# DC_motor_driver.net
KiCad netlist of a schematic drawn in Altium Designer
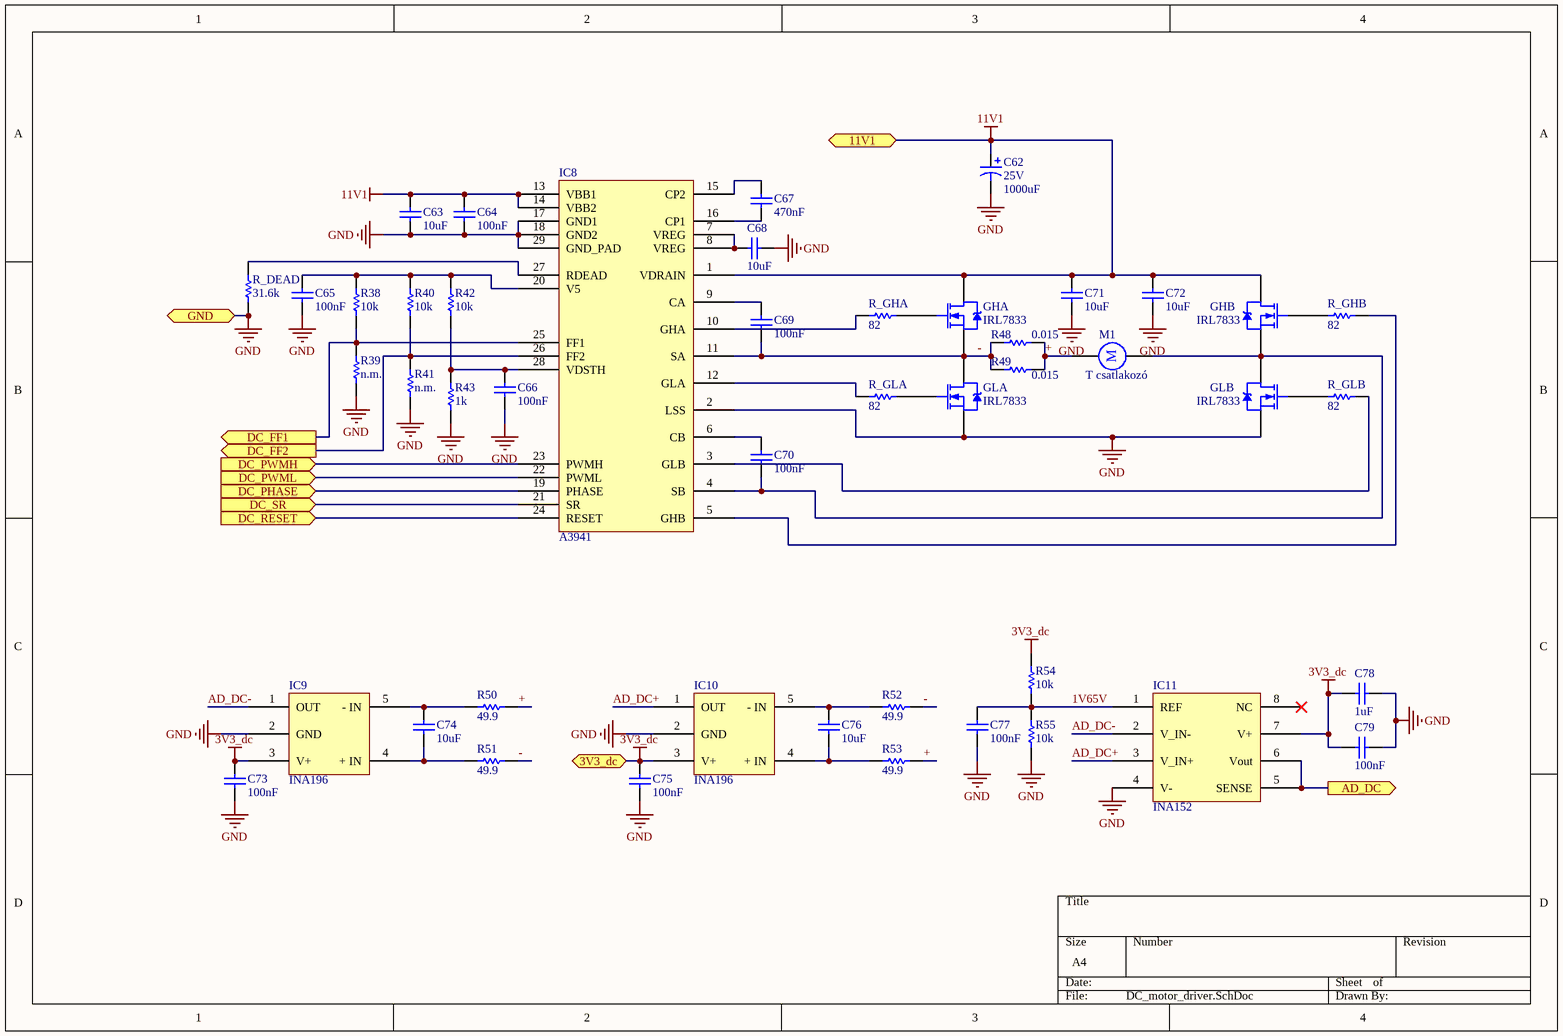
[diagram p0: DC_motor_driver.SchDoc]

(export (version "E")
  (design (tool "Eeschema 10.0.6"))
  (components
    (comp (ref "C62")
      (value "25V")
      (footprint "power_cap_13mm")
      (description "Polarized Capacitor (Radial)")
      (fields (field (name "ALTIUM_VALUE") "1000uF") (field (name "PUBLISHER") "Altium Limited"))
      (libsource (lib "Miscellaneous Devices") (part "Cap Pol1"))
    )
    (comp (ref "C63")
      (value "10uF")
      (footprint "FP_1206_CAP_125")
      (description "Capacitor")
      (fields (field (name "Comment") "Cap") (field (name "PUBLISHER") "Altium Limited"))
      (libsource (lib "Miscellaneous Devices") (part "Cap"))
    )
    (comp (ref "C64")
      (value "100nF")
      (footprint "FP_0603_CAP_080")
      (description "Capacitor")
      (fields (field (name "Comment") "Cap") (field (name "PUBLISHER") "Altium Limited"))
      (libsource (lib "Miscellaneous Devices") (part "Cap"))
    )
    (comp (ref "C65")
      (value "100nF")
      (footprint "FP_0603_CAP_080")
      (description "Capacitor")
      (fields (field (name "Comment") "Cap") (field (name "PUBLISHER") "Altium Limited"))
      (libsource (lib "Miscellaneous Devices") (part "Cap"))
    )
    (comp (ref "C66")
      (value "100nF")
      (footprint "FP_0603_CAP_080")
      (description "Capacitor")
      (fields (field (name "Comment") "Cap") (field (name "PUBLISHER") "Altium Limited"))
      (libsource (lib "Miscellaneous Devices") (part "Cap"))
    )
    (comp (ref "C67")
      (value "470nF")
      (footprint "FP_0603_CAP_080")
      (description "Capacitor")
      (fields (field (name "Comment") "Cap") (field (name "PUBLISHER") "Altium Limited"))
      (libsource (lib "Miscellaneous Devices") (part "Cap"))
    )
    (comp (ref "C68")
      (value "10uF")
      (footprint "FP_1206_CAP_125")
      (description "Capacitor")
      (fields (field (name "Comment") "Cap") (field (name "PUBLISHER") "Altium Limited"))
      (libsource (lib "Miscellaneous Devices") (part "Cap"))
    )
    (comp (ref "C69")
      (value "100nF")
      (footprint "FP_0603_CAP_080")
      (description "Capacitor")
      (fields (field (name "Comment") "Cap") (field (name "PUBLISHER") "Altium Limited"))
      (libsource (lib "Miscellaneous Devices") (part "Cap"))
    )
    (comp (ref "C70")
      (value "100nF")
      (footprint "FP_0603_CAP_080")
      (description "Capacitor")
      (fields (field (name "Comment") "Cap") (field (name "PUBLISHER") "Altium Limited"))
      (libsource (lib "Miscellaneous Devices") (part "Cap"))
    )
    (comp (ref "C71")
      (value "10uF")
      (footprint "FP_1206_CAP_125")
      (description "Capacitor")
      (fields (field (name "Comment") "Cap") (field (name "PUBLISHER") "Altium Limited"))
      (libsource (lib "Miscellaneous Devices") (part "Cap"))
    )
    (comp (ref "C72")
      (value "10uF")
      (footprint "FP_1206_CAP_125")
      (description "Capacitor")
      (fields (field (name "Comment") "Cap") (field (name "PUBLISHER") "Altium Limited"))
      (libsource (lib "Miscellaneous Devices") (part "Cap"))
    )
    (comp (ref "C73")
      (value "100nF")
      (footprint "FP_0603_CAP_080")
      (description "Capacitor")
      (fields (field (name "Comment") "Cap") (field (name "PUBLISHER") "Altium Limited"))
      (libsource (lib "Miscellaneous Devices") (part "Cap"))
    )
    (comp (ref "C74")
      (value "10uF")
      (footprint "FP_0603_CAP_080")
      (description "Capacitor")
      (fields (field (name "Comment") "Cap") (field (name "PUBLISHER") "Altium Limited"))
      (libsource (lib "Miscellaneous Devices") (part "Cap"))
    )
    (comp (ref "C75")
      (value "100nF")
      (footprint "FP_0603_CAP_080")
      (description "Capacitor")
      (fields (field (name "Comment") "Cap") (field (name "PUBLISHER") "Altium Limited"))
      (libsource (lib "Miscellaneous Devices") (part "Cap"))
    )
    (comp (ref "C76")
      (value "10uF")
      (footprint "FP_0603_CAP_080")
      (description "Capacitor")
      (fields (field (name "Comment") "Cap") (field (name "PUBLISHER") "Altium Limited"))
      (libsource (lib "Miscellaneous Devices") (part "Cap"))
    )
    (comp (ref "C77")
      (value "100nF")
      (footprint "FP_0603_CAP_080")
      (description "Capacitor")
      (fields (field (name "Comment") "Cap") (field (name "PUBLISHER") "Altium Limited"))
      (libsource (lib "Miscellaneous Devices") (part "Cap"))
    )
    (comp (ref "C78")
      (value "1uF")
      (footprint "FP_0603_CAP_080")
      (description "Capacitor")
      (fields (field (name "Comment") "Cap") (field (name "PUBLISHER") "Altium Limited"))
      (libsource (lib "Miscellaneous Devices") (part "Cap"))
    )
    (comp (ref "C79")
      (value "100nF")
      (footprint "FP_0603_CAP_080")
      (description "Capacitor")
      (fields (field (name "Comment") "Cap") (field (name "PUBLISHER") "Altium Limited"))
      (libsource (lib "Miscellaneous Devices") (part "Cap"))
    )
    (comp (ref "GHA")
      (value "IRL7833")
      (footprint "TO220AB")
      (description "N-Channel Power MOSFET")
      (fields (field (name "PUBLISHER") "Altium Limited"))
      (libsource (lib "Miscellaneous Devices") (part "NMOS-2"))
    )
    (comp (ref "GHB")
      (value "IRL7833")
      (footprint "TO220AB")
      (description "N-Channel Power MOSFET")
      (fields (field (name "PUBLISHER") "Altium Limited"))
      (libsource (lib "Miscellaneous Devices") (part "NMOS-2"))
    )
    (comp (ref "GLA")
      (value "IRL7833")
      (footprint "TO220AB")
      (description "N-Channel Power MOSFET")
      (fields (field (name "PUBLISHER") "Altium Limited"))
      (libsource (lib "Miscellaneous Devices") (part "NMOS-2"))
    )
    (comp (ref "GLB")
      (value "IRL7833")
      (footprint "TO220AB")
      (description "N-Channel Power MOSFET")
      (fields (field (name "PUBLISHER") "Altium Limited"))
      (libsource (lib "Miscellaneous Devices") (part "NMOS-2"))
    )
    (comp (ref "IC8")
      (value "A3941")
      (footprint "TSSOP28_thermal_pad")
      (libsource (lib "diploma") (part "A3941"))
    )
    (comp (ref "IC9") (value "INA196") (footprint "FP_SOT23-5") (libsource (lib "diploma") (part "INA196")))
    (comp (ref "IC10") (value "INA196") (footprint "FP_SOT23-5") (libsource (lib "diploma") (part "INA196")))
    (comp (ref "IC11") (value "INA152") (footprint "MSOP-MS8_M") (libsource (lib "diploma") (part "INA152")))
    (comp (ref "M1")
      (value "T csatlakozó")
      (footprint "T-csatlakozo")
      (description "Motor, General Kind")
      (fields (field (name "PUBLISHER") "Altium Limited"))
      (libsource (lib "Miscellaneous Devices") (part "Motor"))
    )
    (comp (ref "R38")
      (value "10k")
      (footprint "FP_0603_CAP_080")
      (description "Resistor")
      (fields (field (name "Comment") "Res1") (field (name "PUBLISHER") "Altium Limited"))
      (libsource (lib "Miscellaneous Devices") (part "Res1"))
    )
    (comp (ref "R39")
      (value "n.m.")
      (footprint "FP_0603_CAP_080")
      (description "Resistor")
      (fields (field (name "Comment") "Res1") (field (name "PUBLISHER") "Altium Limited"))
      (libsource (lib "Miscellaneous Devices") (part "Res1"))
    )
    (comp (ref "R40")
      (value "10k")
      (footprint "FP_0603_RES")
      (description "Resistor")
      (fields (field (name "Comment") "Res1") (field (name "PUBLISHER") "Altium Limited"))
      (libsource (lib "Miscellaneous Devices") (part "Res1"))
    )
    (comp (ref "R41")
      (value "n.m.")
      (footprint "FP_0603_RES")
      (description "Resistor")
      (fields (field (name "Comment") "Res1") (field (name "PUBLISHER") "Altium Limited"))
      (libsource (lib "Miscellaneous Devices") (part "Res1"))
    )
    (comp (ref "R42")
      (value "10k")
      (footprint "FP_0603_CAP_080")
      (description "Resistor")
      (fields (field (name "Comment") "Res1") (field (name "PUBLISHER") "Altium Limited"))
      (libsource (lib "Miscellaneous Devices") (part "Res1"))
    )
    (comp (ref "R43")
      (value "1k")
      (footprint "FP_0603_RES")
      (description "Resistor")
      (fields (field (name "Comment") "Res1") (field (name "PUBLISHER") "Altium Limited"))
      (libsource (lib "Miscellaneous Devices") (part "Res1"))
    )
    (comp (ref "R48")
      (value "0.015")
      (footprint "RES_2512")
      (description "Resistor")
      (fields (field (name "Comment") "Res1") (field (name "PUBLISHER") "Altium Limited"))
      (libsource (lib "Miscellaneous Devices") (part "Res1"))
    )
    (comp (ref "R49")
      (value "0.015")
      (footprint "RES_2512")
      (description "Resistor")
      (fields (field (name "Comment") "Res1") (field (name "PUBLISHER") "Altium Limited"))
      (libsource (lib "Miscellaneous Devices") (part "Res1"))
    )
    (comp (ref "R50")
      (value "49.9")
      (footprint "FP_0603_RES")
      (description "Resistor")
      (fields (field (name "Comment") "Res1") (field (name "PUBLISHER") "Altium Limited"))
      (libsource (lib "Miscellaneous Devices") (part "Res1"))
    )
    (comp (ref "R51")
      (value "49.9")
      (footprint "FP_0603_RES")
      (description "Resistor")
      (fields (field (name "Comment") "Res1") (field (name "PUBLISHER") "Altium Limited"))
      (libsource (lib "Miscellaneous Devices") (part "Res1"))
    )
    (comp (ref "R52")
      (value "49.9")
      (footprint "FP_0603_RES")
      (description "Resistor")
      (fields (field (name "Comment") "Res1") (field (name "PUBLISHER") "Altium Limited"))
      (libsource (lib "Miscellaneous Devices") (part "Res1"))
    )
    (comp (ref "R53")
      (value "49.9")
      (footprint "FP_0603_RES")
      (description "Resistor")
      (fields (field (name "Comment") "Res1") (field (name "PUBLISHER") "Altium Limited"))
      (libsource (lib "Miscellaneous Devices") (part "Res1"))
    )
    (comp (ref "R54")
      (value "10k")
      (footprint "FP_0603_RES")
      (description "Resistor")
      (fields (field (name "Comment") "Res1") (field (name "PUBLISHER") "Altium Limited"))
      (libsource (lib "Miscellaneous Devices") (part "Res1"))
    )
    (comp (ref "R55")
      (value "10k")
      (footprint "FP_0603_RES")
      (description "Resistor")
      (fields (field (name "Comment") "Res1") (field (name "PUBLISHER") "Altium Limited"))
      (libsource (lib "Miscellaneous Devices") (part "Res1"))
    )
    (comp (ref "R_DEAD")
      (value "31.6k")
      (footprint "FP_0603_RES")
      (description "Resistor")
      (fields (field (name "Comment") "1us") (field (name "PUBLISHER") "Altium Limited"))
      (libsource (lib "Miscellaneous Devices") (part "Res1"))
    )
    (comp (ref "R_GHA")
      (value "82")
      (footprint "FP_0603_RES")
      (description "Resistor")
      (fields (field (name "Comment") "Res1") (field (name "PUBLISHER") "Altium Limited"))
      (libsource (lib "Miscellaneous Devices") (part "Res1"))
    )
    (comp (ref "R_GHB")
      (value "82")
      (footprint "FP_0603_RES")
      (description "Resistor")
      (fields (field (name "Comment") "Res1") (field (name "PUBLISHER") "Altium Limited"))
      (libsource (lib "Miscellaneous Devices") (part "Res1"))
    )
    (comp (ref "R_GLA")
      (value "82")
      (footprint "FP_0603_RES")
      (description "Resistor")
      (fields (field (name "Comment") "Res1") (field (name "PUBLISHER") "Altium Limited"))
      (libsource (lib "Miscellaneous Devices") (part "Res1"))
    )
    (comp (ref "R_GLB")
      (value "82")
      (footprint "FP_0603_RES")
      (description "Resistor")
      (fields (field (name "Comment") "Res1") (field (name "PUBLISHER") "Altium Limited"))
      (libsource (lib "Miscellaneous Devices") (part "Res1"))
    )
  )
  (nets
    (net (code "1") (name "/+") (class "Default")
      (node (ref "M1") (pin "1") (pinfunction "1_1") (pintype "passive"))
      (node (ref "R48") (pin "2") (pinfunction "2_2") (pintype "passive"))
      (node (ref "R49") (pin "2") (pinfunction "2_2") (pintype "passive"))
      (node (ref "R50") (pin "2") (pinfunction "2_2") (pintype "passive"))
      (node (ref "R53") (pin "2") (pinfunction "2_2") (pintype "passive"))
    )
    (net (code "2") (name "/-") (class "Default")
      (node (ref "C69") (pin "2") (pinfunction "2_2") (pintype "passive"))
      (node (ref "GHA") (pin "3") (pinfunction "S_3") (pintype "passive"))
      (node (ref "GLA") (pin "2") (pinfunction "D_2") (pintype "passive"))
      (node (ref "IC8") (pin "11") (pinfunction "SA_11") (pintype "passive"))
      (node (ref "R48") (pin "1") (pinfunction "1_1") (pintype "passive"))
      (node (ref "R49") (pin "1") (pinfunction "1_1") (pintype "passive"))
      (node (ref "R51") (pin "2") (pinfunction "2_2") (pintype "passive"))
      (node (ref "R52") (pin "2") (pinfunction "2_2") (pintype "passive"))
    )
    (net (code "3") (name "/1V65V") (class "Default")
      (node (ref "C77") (pin "2") (pinfunction "2_2") (pintype "passive"))
      (node (ref "IC11") (pin "1") (pinfunction "REF_1") (pintype "passive"))
      (node (ref "R54") (pin "1") (pinfunction "1_1") (pintype "passive"))
      (node (ref "R55") (pin "2") (pinfunction "2_2") (pintype "passive"))
    )
    (net (code "4") (name "/AD_DC") (class "Default")
      (node (ref "IC11") (pin "5") (pinfunction "SENSE_5") (pintype "passive"))
      (node (ref "IC11") (pin "6") (pinfunction "Vout_6") (pintype "passive"))
    )
    (net (code "5") (name "/AD_DC+") (class "Default")
      (node (ref "IC10") (pin "1") (pinfunction "OUT_1") (pintype "passive"))
      (node (ref "IC11") (pin "3") (pinfunction "V_IN+_3") (pintype "passive"))
    )
    (net (code "6") (name "/AD_DC-") (class "Default")
      (node (ref "IC11") (pin "2") (pinfunction "V_IN-_2") (pintype "passive"))
      (node (ref "IC9") (pin "1") (pinfunction "OUT_1") (pintype "passive"))
    )
    (net (code "7") (name "/DC_FF1") (class "Default")
      (node (ref "IC8") (pin "25") (pinfunction "FF1_25") (pintype "passive"))
      (node (ref "R38") (pin "1") (pinfunction "1_1") (pintype "passive"))
      (node (ref "R39") (pin "2") (pinfunction "2_2") (pintype "passive"))
    )
    (net (code "8") (name "/DC_FF2") (class "Default")
      (node (ref "IC8") (pin "26") (pinfunction "FF2_26") (pintype "passive"))
      (node (ref "R40") (pin "1") (pinfunction "1_1") (pintype "passive"))
      (node (ref "R41") (pin "2") (pinfunction "2_2") (pintype "passive"))
    )
    (net (code "9") (name "/DC_PHASE") (class "Default")
      (node (ref "IC8") (pin "19") (pinfunction "PHASE_19") (pintype "passive"))
    )
    (net (code "10") (name "/DC_PWMH") (class "Default")
      (node (ref "IC8") (pin "23") (pinfunction "PWMH_23") (pintype "passive"))
    )
    (net (code "11") (name "/DC_PWML") (class "Default")
      (node (ref "IC8") (pin "22") (pinfunction "PWML_22") (pintype "passive"))
    )
    (net (code "12") (name "/DC_RESET") (class "Default")
      (node (ref "IC8") (pin "24") (pinfunction "RESET_24") (pintype "passive"))
    )
    (net (code "13") (name "/DC_SR") (class "Default")
      (node (ref "IC8") (pin "21") (pinfunction "SR_21") (pintype "passive"))
    )
    (net (code "14") (name "3V3_dc") (class "Default")
      (node (ref "C73") (pin "2") (pinfunction "2_2") (pintype "passive"))
      (node (ref "C75") (pin "2") (pinfunction "2_2") (pintype "passive"))
      (node (ref "C78") (pin "1") (pinfunction "1_1") (pintype "passive"))
      (node (ref "C79") (pin "1") (pinfunction "1_1") (pintype "passive"))
      (node (ref "IC10") (pin "3") (pinfunction "V+_3") (pintype "passive"))
      (node (ref "IC11") (pin "7") (pinfunction "V+_7") (pintype "passive"))
      (node (ref "IC9") (pin "3") (pinfunction "V+_3") (pintype "passive"))
      (node (ref "R54") (pin "2") (pinfunction "2_2") (pintype "passive"))
    )
    (net (code "15") (name "11V1") (class "Default")
      (node (ref "C62") (pin "1") (pinfunction "1_1") (pintype "passive"))
      (node (ref "C63") (pin "2") (pinfunction "2_2") (pintype "passive"))
      (node (ref "C64") (pin "2") (pinfunction "2_2") (pintype "passive"))
      (node (ref "C71") (pin "1") (pinfunction "1_1") (pintype "passive"))
      (node (ref "C72") (pin "1") (pinfunction "1_1") (pintype "passive"))
      (node (ref "GHA") (pin "2") (pinfunction "D_2") (pintype "passive"))
      (node (ref "GHB") (pin "2") (pinfunction "D_2") (pintype "passive"))
      (node (ref "IC8") (pin "1") (pinfunction "VDRAIN_1") (pintype "passive"))
      (node (ref "IC8") (pin "13") (pinfunction "VBB1_13") (pintype "passive"))
      (node (ref "IC8") (pin "14") (pinfunction "VBB2_14") (pintype "passive"))
    )
    (net (code "16") (name "GND") (class "Default")
      (node (ref "C62") (pin "2") (pinfunction "2_2") (pintype "passive"))
      (node (ref "C63") (pin "1") (pinfunction "1_1") (pintype "passive"))
      (node (ref "C64") (pin "1") (pinfunction "1_1") (pintype "passive"))
      (node (ref "C65") (pin "1") (pinfunction "1_1") (pintype "passive"))
      (node (ref "C66") (pin "1") (pinfunction "1_1") (pintype "passive"))
      (node (ref "C68") (pin "1") (pinfunction "1_1") (pintype "passive"))
      (node (ref "C71") (pin "2") (pinfunction "2_2") (pintype "passive"))
      (node (ref "C72") (pin "2") (pinfunction "2_2") (pintype "passive"))
      (node (ref "C73") (pin "1") (pinfunction "1_1") (pintype "passive"))
      (node (ref "C75") (pin "1") (pinfunction "1_1") (pintype "passive"))
      (node (ref "C77") (pin "1") (pinfunction "1_1") (pintype "passive"))
      (node (ref "C78") (pin "2") (pinfunction "2_2") (pintype "passive"))
      (node (ref "C79") (pin "2") (pinfunction "2_2") (pintype "passive"))
      (node (ref "GLA") (pin "3") (pinfunction "S_3") (pintype "passive"))
      (node (ref "GLB") (pin "3") (pinfunction "S_3") (pintype "passive"))
      (node (ref "IC10") (pin "2") (pinfunction "GND_2") (pintype "passive"))
      (node (ref "IC11") (pin "4") (pinfunction "V-_4") (pintype "passive"))
      (node (ref "IC8") (pin "17") (pinfunction "GND1_17") (pintype "passive"))
      (node (ref "IC8") (pin "18") (pinfunction "GND2_18") (pintype "passive"))
      (node (ref "IC8") (pin "2") (pinfunction "LSS_2") (pintype "passive"))
      (node (ref "IC8") (pin "29") (pinfunction "GND_PAD_29") (pintype "passive"))
      (node (ref "IC9") (pin "2") (pinfunction "GND_2") (pintype "passive"))
      (node (ref "R39") (pin "1") (pinfunction "1_1") (pintype "passive"))
      (node (ref "R41") (pin "1") (pinfunction "1_1") (pintype "passive"))
      (node (ref "R43") (pin "1") (pinfunction "1_1") (pintype "passive"))
      (node (ref "R55") (pin "1") (pinfunction "1_1") (pintype "passive"))
      (node (ref "R_DEAD") (pin "1") (pinfunction "1_1") (pintype "passive"))
    )
    (net (code "17") (name "Net-(C68-Pad2)") (class "Default")
      (node (ref "C68") (pin "2") (pinfunction "2_2") (pintype "passive"))
      (node (ref "IC8") (pin "7") (pinfunction "VREG_7") (pintype "passive"))
      (node (ref "IC8") (pin "8") (pinfunction "VREG_8") (pintype "passive"))
    )
    (net (code "18") (name "Net-(GHA-G)") (class "Default")
      (node (ref "GHA") (pin "1") (pinfunction "G_1") (pintype "passive"))
      (node (ref "R_GHA") (pin "1") (pinfunction "1_1") (pintype "passive"))
    )
    (net (code "19") (name "Net-(GHB-G)") (class "Default")
      (node (ref "GHB") (pin "1") (pinfunction "G_1") (pintype "passive"))
      (node (ref "R_GHB") (pin "2") (pinfunction "2_2") (pintype "passive"))
    )
    (net (code "20") (name "Net-(GHB-S)") (class "Default")
      (node (ref "C70") (pin "2") (pinfunction "2_2") (pintype "passive"))
      (node (ref "GHB") (pin "3") (pinfunction "S_3") (pintype "passive"))
      (node (ref "GLB") (pin "2") (pinfunction "D_2") (pintype "passive"))
      (node (ref "IC8") (pin "4") (pinfunction "SB_4") (pintype "passive"))
      (node (ref "M1") (pin "2") (pinfunction "2_2") (pintype "passive"))
    )
    (net (code "21") (name "Net-(GLA-G)") (class "Default")
      (node (ref "GLA") (pin "1") (pinfunction "G_1") (pintype "passive"))
      (node (ref "R_GLA") (pin "1") (pinfunction "1_1") (pintype "passive"))
    )
    (net (code "22") (name "Net-(GLB-G)") (class "Default")
      (node (ref "GLB") (pin "1") (pinfunction "G_1") (pintype "passive"))
      (node (ref "R_GLB") (pin "2") (pinfunction "2_2") (pintype "passive"))
    )
    (net (code "23") (name "Net-(IC8-CA)") (class "Default")
      (node (ref "C69") (pin "1") (pinfunction "1_1") (pintype "passive"))
      (node (ref "IC8") (pin "9") (pinfunction "CA_9") (pintype "passive"))
    )
    (net (code "24") (name "Net-(IC8-CB)") (class "Default")
      (node (ref "C70") (pin "1") (pinfunction "1_1") (pintype "passive"))
      (node (ref "IC8") (pin "6") (pinfunction "CB_6") (pintype "passive"))
    )
    (net (code "25") (name "Net-(IC8-CP1)") (class "Default")
      (node (ref "C67") (pin "1") (pinfunction "1_1") (pintype "passive"))
      (node (ref "IC8") (pin "16") (pinfunction "CP1_16") (pintype "passive"))
    )
    (net (code "26") (name "Net-(IC8-CP2)") (class "Default")
      (node (ref "C67") (pin "2") (pinfunction "2_2") (pintype "passive"))
      (node (ref "IC8") (pin "15") (pinfunction "CP2_15") (pintype "passive"))
    )
    (net (code "27") (name "Net-(IC8-GHA)") (class "Default")
      (node (ref "IC8") (pin "10") (pinfunction "GHA_10") (pintype "passive"))
      (node (ref "R_GHA") (pin "2") (pinfunction "2_2") (pintype "passive"))
    )
    (net (code "28") (name "Net-(IC8-GHB)") (class "Default")
      (node (ref "IC8") (pin "5") (pinfunction "GHB_5") (pintype "passive"))
      (node (ref "R_GHB") (pin "1") (pinfunction "1_1") (pintype "passive"))
    )
    (net (code "29") (name "Net-(IC8-GLA)") (class "Default")
      (node (ref "IC8") (pin "12") (pinfunction "GLA_12") (pintype "passive"))
      (node (ref "R_GLA") (pin "2") (pinfunction "2_2") (pintype "passive"))
    )
    (net (code "30") (name "Net-(IC8-GLB)") (class "Default")
      (node (ref "IC8") (pin "3") (pinfunction "GLB_3") (pintype "passive"))
      (node (ref "R_GLB") (pin "1") (pinfunction "1_1") (pintype "passive"))
    )
    (net (code "31") (name "Net-(IC8-RDEAD)") (class "Default")
      (node (ref "IC8") (pin "27") (pinfunction "RDEAD_27") (pintype "passive"))
      (node (ref "R_DEAD") (pin "2") (pinfunction "2_2") (pintype "passive"))
    )
    (net (code "32") (name "Net-(IC8-V5)") (class "Default")
      (node (ref "C65") (pin "2") (pinfunction "2_2") (pintype "passive"))
      (node (ref "IC8") (pin "20") (pinfunction "V5_20") (pintype "passive"))
      (node (ref "R38") (pin "2") (pinfunction "2_2") (pintype "passive"))
      (node (ref "R40") (pin "2") (pinfunction "2_2") (pintype "passive"))
      (node (ref "R42") (pin "2") (pinfunction "2_2") (pintype "passive"))
    )
    (net (code "33") (name "Net-(IC8-VDSTH)") (class "Default")
      (node (ref "C66") (pin "2") (pinfunction "2_2") (pintype "passive"))
      (node (ref "IC8") (pin "28") (pinfunction "VDSTH_28") (pintype "passive"))
      (node (ref "R42") (pin "1") (pinfunction "1_1") (pintype "passive"))
      (node (ref "R43") (pin "2") (pinfunction "2_2") (pintype "passive"))
    )
    (net (code "34") (name "Net-(IC9-+_IN)") (class "Default")
      (node (ref "C74") (pin "1") (pinfunction "1_1") (pintype "passive"))
      (node (ref "IC9") (pin "4") (pinfunction "+_IN_4") (pintype "passive"))
      (node (ref "R51") (pin "1") (pinfunction "1_1") (pintype "passive"))
    )
    (net (code "35") (name "Net-(IC9--_IN)") (class "Default")
      (node (ref "C74") (pin "2") (pinfunction "2_2") (pintype "passive"))
      (node (ref "IC9") (pin "5") (pinfunction "-_IN_5") (pintype "passive"))
      (node (ref "R50") (pin "1") (pinfunction "1_1") (pintype "passive"))
    )
    (net (code "36") (name "Net-(IC10-+_IN)") (class "Default")
      (node (ref "C76") (pin "1") (pinfunction "1_1") (pintype "passive"))
      (node (ref "IC10") (pin "4") (pinfunction "+_IN_4") (pintype "passive"))
      (node (ref "R53") (pin "1") (pinfunction "1_1") (pintype "passive"))
    )
    (net (code "37") (name "Net-(IC10--_IN)") (class "Default")
      (node (ref "C76") (pin "2") (pinfunction "2_2") (pintype "passive"))
      (node (ref "IC10") (pin "5") (pinfunction "-_IN_5") (pintype "passive"))
      (node (ref "R52") (pin "1") (pinfunction "1_1") (pintype "passive"))
    )
    (net (code "38") (name "unconnected-(IC11-NC-Pad8)") (class "Default")
      (node (ref "IC11") (pin "8") (pinfunction "NC_8") (pintype "passive+no_connect"))
    )
  )
)
